# SimpleIO.net
KiCad netlist of a schematic drawn in EAGLE
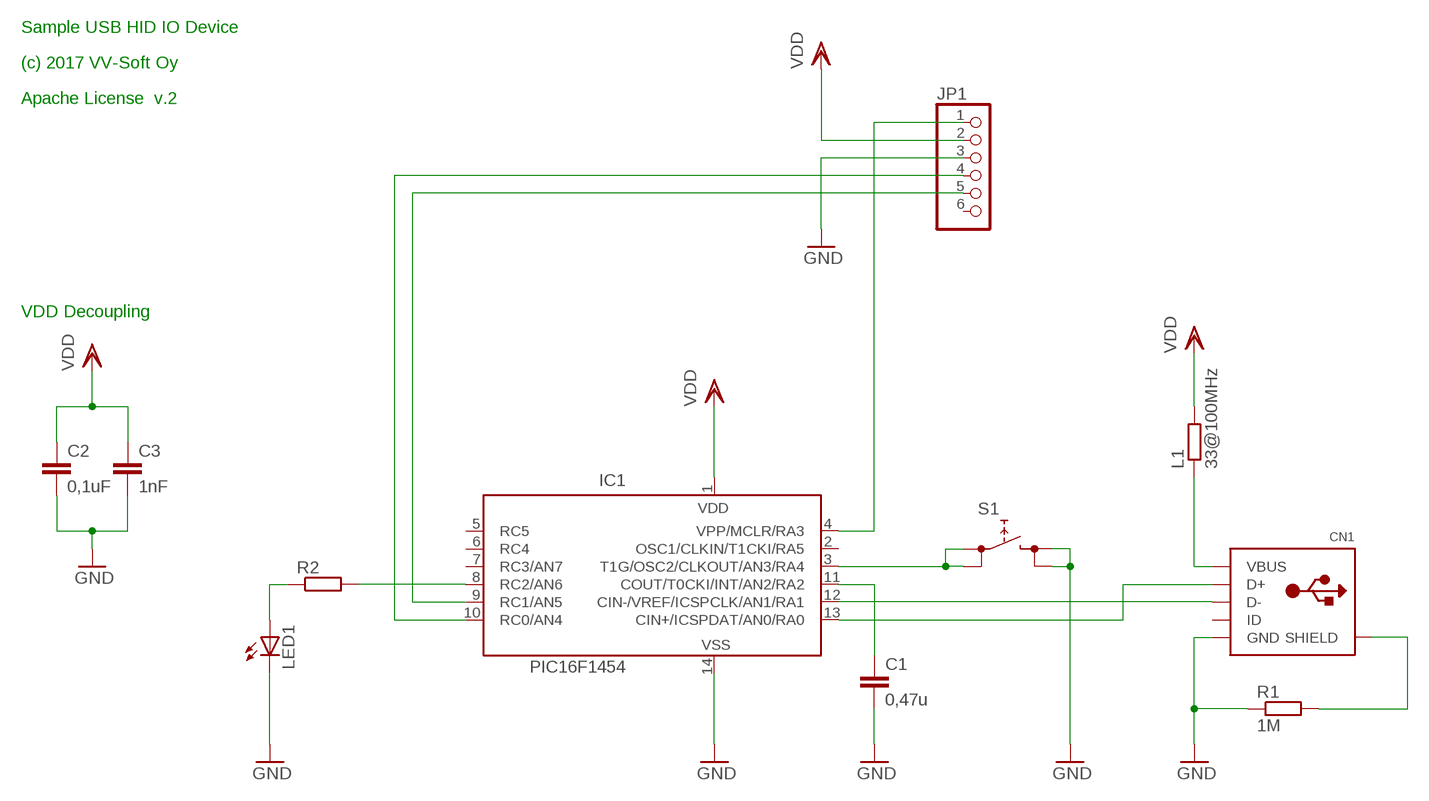
[diagram p0: schematic, sheet 1]

(export (version "E")
  (design (tool "Eeschema 10.0.6"))
  (components
    (comp (ref "C1")
      (value "0,47u")
      (footprint "eagle-import:C0603")
      (libsource (lib "eagle-import") (part "C-EUC0603"))
    )
    (comp (ref "C2")
      (value "0,1uF")
      (footprint "eagle-import:C0603")
      (libsource (lib "eagle-import") (part "C-EUC0603"))
    )
    (comp (ref "C3")
      (value "1nF")
      (footprint "eagle-import:C0603")
      (libsource (lib "eagle-import") (part "C-EUC0603"))
    )
    (comp (ref "CN1")
      (value "USBMICROB")
      (footprint "eagle-import:USB-MICROB")
      (libsource (lib "eagle-import") (part "USBMICROB"))
    )
    (comp (ref "IC1")
      (value "PIC16F1454")
      (footprint "eagle-import:SO-14")
      (libsource (lib "eagle-import") (part "PIC16F1503SL"))
    )
    (comp (ref "JP1")
      (value "PINHD-1X6")
      (footprint "eagle-import:1X06")
      (libsource (lib "eagle-import") (part "PINHD-1X6"))
    )
    (comp (ref "L1")
      (value "33@100MHz")
      (footprint "eagle-import:R0603")
      (libsource (lib "eagle-import") (part "R-EU_R0603"))
    )
    (comp (ref "LED1")
      (value "LED")
      (footprint "eagle-import:SMARTLED-TTW")
      (libsource (lib "eagle-import") (part "LED"))
    )
    (comp (ref "R1")
      (value "1M")
      (footprint "eagle-import:R0603")
      (libsource (lib "eagle-import") (part "R-EU_R0603"))
    )
    (comp (ref "R2")
      (value "R-EU_R0603")
      (footprint "eagle-import:R0603")
      (libsource (lib "eagle-import") (part "R-EU_R0603"))
    )
    (comp (ref "S1")
      (value "REKN")
      (footprint "eagle-import:REKN")
      (libsource (lib "eagle-import") (part "REKN"))
    )
  )
  (nets
    (net (code "1") (name "GND") (class "Default")
      (node (ref "C1") (pin "2") (pinfunction "2_2") (pintype "passive"))
      (node (ref "C2") (pin "2") (pinfunction "2_2") (pintype "passive"))
      (node (ref "C3") (pin "2") (pinfunction "2_2") (pintype "passive"))
      (node (ref "CN1") (pin "P5") (pinfunction "GND_P5") (pintype "power_in"))
      (node (ref "IC1") (pin "14") (pinfunction "VSS_14") (pintype "power_in"))
      (node (ref "JP1") (pin "3") (pinfunction "3_3") (pintype "passive"))
      (node (ref "LED1") (pin "C@1") (pinfunction "C_C@1") (pintype "passive"))
      (node (ref "R1") (pin "1") (pinfunction "1_1") (pintype "passive"))
      (node (ref "S1") (pin "1A") (pinfunction "1_1A") (pintype "passive"))
      (node (ref "S1") (pin "1B") (pinfunction "1_1B") (pintype "passive"))
    )
    (net (code "2") (name "Net-(CN1-D+)") (class "Default")
      (node (ref "CN1") (pin "P3") (pinfunction "D+_P3") (pintype "bidirectional"))
      (node (ref "IC1") (pin "13") (pinfunction "CIN+/ICSPDAT/AN0/RA0_13") (pintype "bidirectional"))
    )
    (net (code "3") (name "Net-(CN1-D-)") (class "Default")
      (node (ref "CN1") (pin "P2") (pinfunction "D-_P2") (pintype "bidirectional"))
      (node (ref "IC1") (pin "12") (pinfunction "CIN-/VREF/ICSPCLK/AN1/RA1_12") (pintype "bidirectional"))
    )
    (net (code "4") (name "Net-(CN1-SHIELD-PadPAD-LB)") (class "Default")
      (node (ref "CN1") (pin "PAD-LB") (pinfunction "SHIELD_PAD-LB") (pintype "bidirectional"))
      (node (ref "CN1") (pin "PAD-LLB") (pinfunction "SHIELD_PAD-LLB") (pintype "bidirectional"))
      (node (ref "CN1") (pin "PAD-LT") (pinfunction "SHIELD_PAD-LT") (pintype "bidirectional"))
      (node (ref "CN1") (pin "PAD-RB") (pinfunction "SHIELD_PAD-RB") (pintype "bidirectional"))
      (node (ref "CN1") (pin "PAD-RRB") (pinfunction "SHIELD_PAD-RRB") (pintype "bidirectional"))
      (node (ref "CN1") (pin "PAD-RT") (pinfunction "SHIELD_PAD-RT") (pintype "bidirectional"))
      (node (ref "R1") (pin "2") (pinfunction "2_2") (pintype "passive"))
    )
    (net (code "5") (name "Net-(CN1-VBUS)") (class "Default")
      (node (ref "CN1") (pin "P1") (pinfunction "VBUS_P1") (pintype "power_in"))
      (node (ref "L1") (pin "1") (pinfunction "1_1") (pintype "passive"))
    )
    (net (code "6") (name "Net-(IC1-COUT{slash}T0CKI{slash}INT{slash}AN2{slash}RA2)") (class "Default")
      (node (ref "C1") (pin "1") (pinfunction "1_1") (pintype "passive"))
      (node (ref "IC1") (pin "11") (pinfunction "COUT/T0CKI/INT/AN2/RA2_11") (pintype "bidirectional"))
    )
    (net (code "7") (name "Net-(IC1-RC0{slash}AN4)") (class "Default")
      (node (ref "IC1") (pin "10") (pinfunction "RC0/AN4_10") (pintype "bidirectional"))
      (node (ref "JP1") (pin "4") (pinfunction "4_4") (pintype "passive"))
    )
    (net (code "8") (name "Net-(IC1-RC1{slash}AN5)") (class "Default")
      (node (ref "IC1") (pin "9") (pinfunction "RC1/AN5_9") (pintype "bidirectional"))
      (node (ref "JP1") (pin "5") (pinfunction "5_5") (pintype "passive"))
    )
    (net (code "9") (name "Net-(IC1-RC2{slash}AN6)") (class "Default")
      (node (ref "IC1") (pin "8") (pinfunction "RC2/AN6_8") (pintype "bidirectional"))
      (node (ref "R2") (pin "2") (pinfunction "2_2") (pintype "passive"))
    )
    (net (code "10") (name "Net-(IC1-T1G{slash}OSC2{slash}CLKOUT{slash}AN3{slash}RA4)") (class "Default")
      (node (ref "IC1") (pin "3") (pinfunction "T1G/OSC2/CLKOUT/AN3/RA4_3") (pintype "bidirectional"))
      (node (ref "S1") (pin "0A") (pinfunction "0_0A") (pintype "passive"))
      (node (ref "S1") (pin "0B") (pinfunction "0_0B") (pintype "passive"))
    )
    (net (code "11") (name "Net-(IC1-VPP{slash}MCLR{slash}RA3)") (class "Default")
      (node (ref "IC1") (pin "4") (pinfunction "VPP/MCLR/RA3_4") (pintype "input"))
      (node (ref "JP1") (pin "1") (pinfunction "1_1") (pintype "passive"))
    )
    (net (code "12") (name "Net-(LED1-A)") (class "Default")
      (node (ref "LED1") (pin "A@1") (pinfunction "A_A@1") (pintype "passive"))
      (node (ref "R2") (pin "1") (pinfunction "1_1") (pintype "passive"))
    )
    (net (code "13") (name "VDD") (class "Default")
      (node (ref "C2") (pin "1") (pinfunction "1_1") (pintype "passive"))
      (node (ref "C3") (pin "1") (pinfunction "1_1") (pintype "passive"))
      (node (ref "IC1") (pin "1") (pinfunction "VDD_1") (pintype "power_in"))
      (node (ref "JP1") (pin "2") (pinfunction "2_2") (pintype "passive"))
      (node (ref "L1") (pin "2") (pinfunction "2_2") (pintype "passive"))
    )
    (net (code "14") (name "unconnected-(CN1-ID-PadP4)") (class "Default")
      (node (ref "CN1") (pin "P4") (pinfunction "ID_P4") (pintype "bidirectional"))
    )
    (net (code "15") (name "unconnected-(IC1-OSC1{slash}CLKIN{slash}T1CKI{slash}RA5-Pad2)") (class "Default")
      (node (ref "IC1") (pin "2") (pinfunction "OSC1/CLKIN/T1CKI/RA5_2") (pintype "bidirectional"))
    )
    (net (code "16") (name "unconnected-(IC1-RC3{slash}AN7-Pad7)") (class "Default")
      (node (ref "IC1") (pin "7") (pinfunction "RC3/AN7_7") (pintype "bidirectional"))
    )
    (net (code "17") (name "unconnected-(IC1-RC4-Pad6)") (class "Default")
      (node (ref "IC1") (pin "6") (pinfunction "RC4_6") (pintype "bidirectional"))
    )
    (net (code "18") (name "unconnected-(IC1-RC5-Pad5)") (class "Default")
      (node (ref "IC1") (pin "5") (pinfunction "RC5_5") (pintype "bidirectional"))
    )
    (net (code "19") (name "unconnected-(JP1-Pad6)") (class "Default")
      (node (ref "JP1") (pin "6") (pinfunction "6_6") (pintype "passive"))
    )
  )
)
